# P_JTAG_EEPROM.net
KiCad netlist of a schematic drawn in Altium Designer
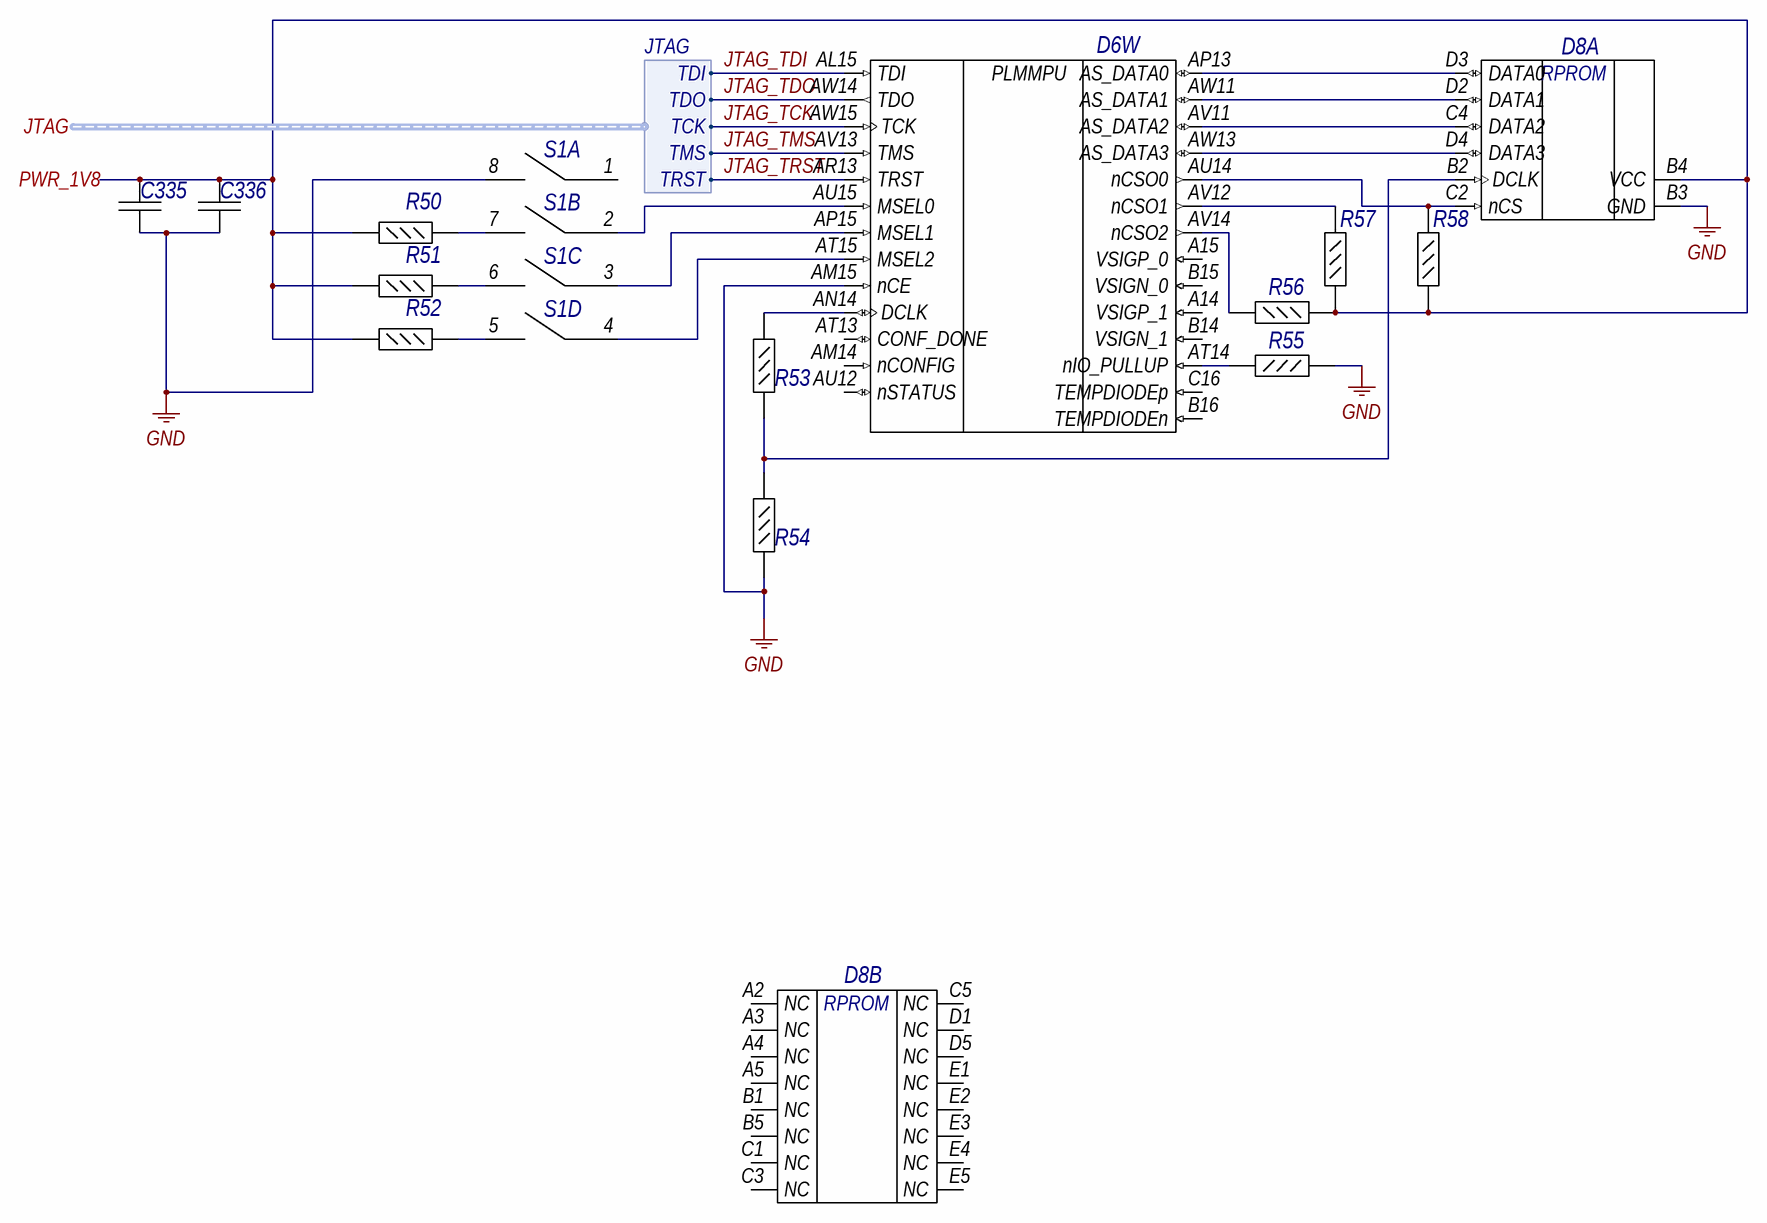
[diagram p0: P_JTAG_EEPROM.SchDoc]

(export (version "E")
  (design (tool "Eeschema 10.0.6"))
  (components
    (comp (ref "C335")
      (value "C1005X7R1E104M")
      (footprint "CAPC1005X55X10LL05")
      (description "Chip Capacitor, 0.1 uF, +/- 20%, 25 V, -55 to 125 degC, 0402 (1005 Metric), RoHS, Tape and Reel")
      (fields (field (name "TOLERANCE") "20%"))
      (libsource (lib "MiniPC DB") (part "CAP_NP"))
    )
    (comp (ref "C336")
      (value "C1005X7R1E104M")
      (footprint "CAPC1005X55X10LL05")
      (description "Chip Capacitor, 0.1 uF, +/- 20%, 25 V, -55 to 125 degC, 0402 (1005 Metric), RoHS, Tape and Reel")
      (fields (field (name "TOLERANCE") "20%"))
      (libsource (lib "MiniPC DB") (part "CAP_NP"))
    )
    (comp (ref "D6")
      (value "10AS066N3F40E2SGE2")
      (footprint "ALTR-FBGA1517_A-350")
      (libsource (lib "MiniPC DB") (part "10AS066N3F40"))
    )
    (comp (ref "D8")
      (value "EPCQL1024F24IN")
      (footprint "ALTR-FBGA24_A-130")
      (description "EPCQ-L Serial Configuration Device, 1.8 V, -40 to 85 degC, 24-Pin FBGA, RoHS, Tray")
      (fields (field (name "MANUFACTURER") "Altera"))
      (libsource (lib "MiniPC DB") (part "EPCQLXXX"))
    )
    (comp (ref "R50")
      (value "ERJ-2RKF1001X")
      (footprint "RESC1005X40X25LL05T05")
      (description "Chip Resistor, 1 KOhm, +/- 1%, 100 mW, -55 to 155 degC, 0402 (1005 Metric), RoHS, Tape and Reel")
      (fields (field (name "TOLERANCE") "1%") (field (name "MANUFACTURER") "Basic Passives"))
      (libsource (lib "MiniPC DB") (part "RES-0.05"))
    )
    (comp (ref "R51")
      (value "ERJ-2RKF1001X")
      (footprint "RESC1005X40X25LL05T05")
      (description "Chip Resistor, 1 KOhm, +/- 1%, 100 mW, -55 to 155 degC, 0402 (1005 Metric), RoHS, Tape and Reel")
      (fields (field (name "TOLERANCE") "1%") (field (name "MANUFACTURER") "Basic Passives"))
      (libsource (lib "MiniPC DB") (part "RES-0.05"))
    )
    (comp (ref "R52")
      (value "ERJ-2RKF1001X")
      (footprint "RESC1005X40X25LL05T05")
      (description "Chip Resistor, 1 KOhm, +/- 1%, 100 mW, -55 to 155 degC, 0402 (1005 Metric), RoHS, Tape and Reel")
      (fields (field (name "TOLERANCE") "1%") (field (name "MANUFACTURER") "Basic Passives"))
      (libsource (lib "MiniPC DB") (part "RES-0.05"))
    )
    (comp (ref "R53")
      (value "ERJ-2RKF1002X")
      (footprint "RESC1005X40X25LL05T05")
      (description "Chip Resistor, 10 KOhm, +/- 1%, 100 mW, -55 to 155 degC, 0402 (1005 Metric), RoHS, Tape and Reel")
      (fields (field (name "TOLERANCE") "1%") (field (name "MANUFACTURER") "Basic Passives"))
      (libsource (lib "") (part "RES-0.05_1"))
    )
    (comp (ref "R54")
      (value "ERJ-2RKF1002X")
      (footprint "RESC1005X40X25LL05T05")
      (description "Chip Resistor, 10 KOhm, +/- 1%, 100 mW, -55 to 155 degC, 0402 (1005 Metric), RoHS, Tape and Reel")
      (fields (field (name "TOLERANCE") "1%") (field (name "MANUFACTURER") "Basic Passives"))
      (libsource (lib "") (part "RES-0.05_1"))
    )
    (comp (ref "R55")
      (value "ERJ-2GE0R00X")
      (footprint "RESC1005X40X25LL05T05")
      (description "Chip Resistor, 0 mOhm, +/- 5%, 100 mW, -55 to 155 degC, 0402 (1005 Metric), RoHS, Tape and Reel")
      (fields (field (name "TOLERANCE") "5%") (field (name "MANUFACTURER") "Basic Passives"))
      (libsource (lib "") (part "RES-0.05_3"))
    )
    (comp (ref "R56")
      (value "ERJ-2RKF1002X")
      (footprint "RESC1005X40X25LL05T05")
      (description "Chip Resistor, 10 KOhm, +/- 1%, 100 mW, -55 to 155 degC, 0402 (1005 Metric), RoHS, Tape and Reel")
      (fields (field (name "TOLERANCE") "1%") (field (name "MANUFACTURER") "Basic Passives"))
      (libsource (lib "") (part "RES-0.05_2"))
    )
    (comp (ref "R57")
      (value "ERJ-2RKF1002X")
      (footprint "RESC1005X40X25LL05T05")
      (description "Chip Resistor, 10 KOhm, +/- 1%, 100 mW, -55 to 155 degC, 0402 (1005 Metric), RoHS, Tape and Reel")
      (fields (field (name "TOLERANCE") "1%") (field (name "MANUFACTURER") "Basic Passives"))
      (libsource (lib "") (part "RES-0.05_1"))
    )
    (comp (ref "R58")
      (value "ERJ-2RKF1002X")
      (footprint "RESC1005X40X25LL05T05")
      (description "Chip Resistor, 10 KOhm, +/- 1%, 100 mW, -55 to 155 degC, 0402 (1005 Metric), RoHS, Tape and Reel")
      (fields (field (name "TOLERANCE") "1%") (field (name "MANUFACTURER") "Basic Passives"))
      (libsource (lib "") (part "RES-0.05_1"))
    )
    (comp (ref "S1")
      (value "416131160804")
      (footprint "416131160804")
      (description "WS-DISV 1.27 mm small compact SMD Dip Switch with top tape")
      (fields (field (name "MANUFACTURER") "Wuerth Elektronik"))
      (libsource (lib "MiniPC DB") (part "SW_SPST_4"))
    )
  )
  (nets
    (net (code "2") (name "/JTAG_TCK") (class "Default")
      (node (ref "D6") (pin "AW15") (pinfunction "TCK_AW15") (pintype "input"))
    )
    (net (code "3") (name "/JTAG_TDI") (class "Default")
      (node (ref "D6") (pin "AL15") (pinfunction "TDI_AL15") (pintype "input"))
    )
    (net (code "4") (name "/JTAG_TDO") (class "Default")
      (node (ref "D6") (pin "AW14") (pinfunction "TDO_AW14") (pintype "output"))
    )
    (net (code "5") (name "/JTAG_TMS") (class "Default")
      (node (ref "D6") (pin "AV13") (pinfunction "TMS_AV13") (pintype "input"))
    )
    (net (code "6") (name "/JTAG_TRST") (class "Default")
      (node (ref "D6") (pin "AR13") (pinfunction "TRST_AR13") (pintype "input"))
    )
    (net (code "7") (name "/PWR_1V8") (class "Default")
      (node (ref "C335") (pin "2") (pinfunction "2_2") (pintype "passive"))
      (node (ref "C336") (pin "2") (pinfunction "2_2") (pintype "passive"))
      (node (ref "D8") (pin "B4") (pinfunction "VCC_B4") (pintype "passive"))
      (node (ref "R50") (pin "1") (pinfunction "1_1") (pintype "passive"))
      (node (ref "R51") (pin "1") (pinfunction "1_1") (pintype "passive"))
      (node (ref "R52") (pin "1") (pinfunction "1_1") (pintype "passive"))
      (node (ref "R56") (pin "1") (pinfunction "1_1") (pintype "passive"))
      (node (ref "R57") (pin "1") (pinfunction "1_1") (pintype "passive"))
      (node (ref "R58") (pin "1") (pinfunction "1_1") (pintype "passive"))
    )
    (net (code "9") (name "GND") (class "Default")
      (node (ref "C335") (pin "1") (pinfunction "1_1") (pintype "passive"))
      (node (ref "C336") (pin "1") (pinfunction "1_1") (pintype "passive"))
      (node (ref "D6") (pin "AM15") (pinfunction "nCE_AM15") (pintype "input"))
      (node (ref "D8") (pin "B3") (pinfunction "GND_B3") (pintype "passive"))
      (node (ref "R54") (pin "1") (pinfunction "1_1") (pintype "passive"))
      (node (ref "R55") (pin "1") (pinfunction "1_1") (pintype "passive"))
      (node (ref "S1") (pin "8") (pinfunction "8_8") (pintype "passive"))
    )
    (net (code "10") (name "Net-(D6W-AS_DATA0)") (class "Default")
      (node (ref "D6") (pin "AP13") (pinfunction "AS_DATA0_AP13") (pintype "bidirectional"))
      (node (ref "D8") (pin "D3") (pinfunction "DATA0_D3") (pintype "bidirectional"))
    )
    (net (code "11") (name "Net-(D6W-AS_DATA1)") (class "Default")
      (node (ref "D6") (pin "AW11") (pinfunction "AS_DATA1_AW11") (pintype "bidirectional"))
      (node (ref "D8") (pin "D2") (pinfunction "DATA1_D2") (pintype "bidirectional"))
    )
    (net (code "12") (name "Net-(D6W-AS_DATA2)") (class "Default")
      (node (ref "D6") (pin "AV11") (pinfunction "AS_DATA2_AV11") (pintype "bidirectional"))
      (node (ref "D8") (pin "C4") (pinfunction "DATA2_C4") (pintype "bidirectional"))
    )
    (net (code "13") (name "Net-(D6W-AS_DATA3)") (class "Default")
      (node (ref "D6") (pin "AW13") (pinfunction "AS_DATA3_AW13") (pintype "bidirectional"))
      (node (ref "D8") (pin "D4") (pinfunction "DATA3_D4") (pintype "bidirectional"))
    )
    (net (code "14") (name "Net-(D6W-DCLK)") (class "Default")
      (node (ref "D6") (pin "AN14") (pinfunction "DCLK_AN14") (pintype "bidirectional"))
      (node (ref "R53") (pin "2") (pinfunction "2_2") (pintype "passive"))
    )
    (net (code "15") (name "Net-(D6W-MSEL0)") (class "Default")
      (node (ref "D6") (pin "AU15") (pinfunction "MSEL0_AU15") (pintype "input"))
      (node (ref "S1") (pin "2") (pinfunction "2_2") (pintype "passive"))
    )
    (net (code "16") (name "Net-(D6W-MSEL1)") (class "Default")
      (node (ref "D6") (pin "AP15") (pinfunction "MSEL1_AP15") (pintype "input"))
      (node (ref "S1") (pin "3") (pinfunction "3_3") (pintype "passive"))
    )
    (net (code "17") (name "Net-(D6W-MSEL2)") (class "Default")
      (node (ref "D6") (pin "AT15") (pinfunction "MSEL2_AT15") (pintype "input"))
      (node (ref "S1") (pin "4") (pinfunction "4_4") (pintype "passive"))
    )
    (net (code "18") (name "Net-(D6W-nCSO0)") (class "Default")
      (node (ref "D6") (pin "AU14") (pinfunction "nCSO0_AU14") (pintype "output"))
      (node (ref "D8") (pin "C2") (pinfunction "nCS_C2") (pintype "input"))
      (node (ref "R58") (pin "2") (pinfunction "2_2") (pintype "passive"))
    )
    (net (code "19") (name "Net-(D6W-nCSO1)") (class "Default")
      (node (ref "D6") (pin "AV12") (pinfunction "nCSO1_AV12") (pintype "output"))
      (node (ref "R57") (pin "2") (pinfunction "2_2") (pintype "passive"))
    )
    (net (code "20") (name "Net-(D6W-nCSO2)") (class "Default")
      (node (ref "D6") (pin "AV14") (pinfunction "nCSO2_AV14") (pintype "output"))
      (node (ref "R56") (pin "2") (pinfunction "2_2") (pintype "passive"))
    )
    (net (code "21") (name "Net-(D6W-nIO_PULLUP)") (class "Default")
      (node (ref "D6") (pin "AT14") (pinfunction "nIO_PULLUP_AT14") (pintype "input"))
      (node (ref "R55") (pin "2") (pinfunction "2_2") (pintype "passive"))
    )
    (net (code "22") (name "Net-(D8A-DCLK)") (class "Default")
      (node (ref "D8") (pin "B2") (pinfunction "DCLK_B2") (pintype "input"))
      (node (ref "R53") (pin "1") (pinfunction "1_1") (pintype "passive"))
      (node (ref "R54") (pin "2") (pinfunction "2_2") (pintype "passive"))
    )
    (net (code "23") (name "Net-(R50-Pad2)") (class "Default")
      (node (ref "R50") (pin "2") (pinfunction "2_2") (pintype "passive"))
      (node (ref "S1") (pin "7") (pinfunction "7_7") (pintype "passive"))
    )
    (net (code "24") (name "Net-(R51-Pad2)") (class "Default")
      (node (ref "R51") (pin "2") (pinfunction "2_2") (pintype "passive"))
      (node (ref "S1") (pin "6") (pinfunction "6_6") (pintype "passive"))
    )
    (net (code "25") (name "Net-(R52-Pad2)") (class "Default")
      (node (ref "R52") (pin "2") (pinfunction "2_2") (pintype "passive"))
      (node (ref "S1") (pin "5") (pinfunction "5_5") (pintype "passive"))
    )
    (net (code "26") (name "unconnected-(D6W-CONF_DONE-PadAT13)") (class "Default")
      (node (ref "D6") (pin "AT13") (pinfunction "CONF_DONE_AT13") (pintype "bidirectional"))
    )
    (net (code "27") (name "unconnected-(D6W-TEMPDIODEn-PadB16)") (class "Default")
      (node (ref "D6") (pin "B16") (pinfunction "TEMPDIODEn_B16") (pintype "input"))
    )
    (net (code "28") (name "unconnected-(D6W-TEMPDIODEp-PadC16)") (class "Default")
      (node (ref "D6") (pin "C16") (pinfunction "TEMPDIODEp_C16") (pintype "input"))
    )
    (net (code "29") (name "unconnected-(D6W-VSIGN_0-PadB15)") (class "Default")
      (node (ref "D6") (pin "B15") (pinfunction "VSIGN_0_B15") (pintype "input"))
    )
    (net (code "30") (name "unconnected-(D6W-VSIGN_1-PadB14)") (class "Default")
      (node (ref "D6") (pin "B14") (pinfunction "VSIGN_1_B14") (pintype "input"))
    )
    (net (code "31") (name "unconnected-(D6W-VSIGP_0-PadA15)") (class "Default")
      (node (ref "D6") (pin "A15") (pinfunction "VSIGP_0_A15") (pintype "input"))
    )
    (net (code "32") (name "unconnected-(D6W-VSIGP_1-PadA14)") (class "Default")
      (node (ref "D6") (pin "A14") (pinfunction "VSIGP_1_A14") (pintype "input"))
    )
    (net (code "33") (name "unconnected-(D6W-nCONFIG-PadAM14)") (class "Default")
      (node (ref "D6") (pin "AM14") (pinfunction "nCONFIG_AM14") (pintype "input"))
    )
    (net (code "34") (name "unconnected-(D6W-nSTATUS-PadAU12)") (class "Default")
      (node (ref "D6") (pin "AU12") (pinfunction "nSTATUS_AU12") (pintype "bidirectional"))
    )
    (net (code "35") (name "unconnected-(D8B-NC-PadA2)") (class "Default")
      (node (ref "D8") (pin "A2") (pinfunction "NC_A2") (pintype "passive"))
    )
    (net (code "36") (name "unconnected-(D8B-NC-PadA3)") (class "Default")
      (node (ref "D8") (pin "A3") (pinfunction "NC_A3") (pintype "passive"))
    )
    (net (code "37") (name "unconnected-(D8B-NC-PadA4)") (class "Default")
      (node (ref "D8") (pin "A4") (pinfunction "NC_A4") (pintype "passive"))
    )
    (net (code "38") (name "unconnected-(D8B-NC-PadA5)") (class "Default")
      (node (ref "D8") (pin "A5") (pinfunction "NC_A5") (pintype "passive"))
    )
    (net (code "39") (name "unconnected-(D8B-NC-PadB1)") (class "Default")
      (node (ref "D8") (pin "B1") (pinfunction "NC_B1") (pintype "passive"))
    )
    (net (code "40") (name "unconnected-(D8B-NC-PadB5)") (class "Default")
      (node (ref "D8") (pin "B5") (pinfunction "NC_B5") (pintype "passive"))
    )
    (net (code "41") (name "unconnected-(D8B-NC-PadC1)") (class "Default")
      (node (ref "D8") (pin "C1") (pinfunction "NC_C1") (pintype "passive"))
    )
    (net (code "42") (name "unconnected-(D8B-NC-PadC3)") (class "Default")
      (node (ref "D8") (pin "C3") (pinfunction "NC_C3") (pintype "passive"))
    )
    (net (code "43") (name "unconnected-(D8B-NC-PadC5)") (class "Default")
      (node (ref "D8") (pin "C5") (pinfunction "NC_C5") (pintype "passive"))
    )
    (net (code "44") (name "unconnected-(D8B-NC-PadD1)") (class "Default")
      (node (ref "D8") (pin "D1") (pinfunction "NC_D1") (pintype "passive"))
    )
    (net (code "45") (name "unconnected-(D8B-NC-PadD5)") (class "Default")
      (node (ref "D8") (pin "D5") (pinfunction "NC_D5") (pintype "passive"))
    )
    (net (code "46") (name "unconnected-(D8B-NC-PadE1)") (class "Default")
      (node (ref "D8") (pin "E1") (pinfunction "NC_E1") (pintype "passive"))
    )
    (net (code "47") (name "unconnected-(D8B-NC-PadE2)") (class "Default")
      (node (ref "D8") (pin "E2") (pinfunction "NC_E2") (pintype "passive"))
    )
    (net (code "48") (name "unconnected-(D8B-NC-PadE3)") (class "Default")
      (node (ref "D8") (pin "E3") (pinfunction "NC_E3") (pintype "passive"))
    )
    (net (code "49") (name "unconnected-(D8B-NC-PadE4)") (class "Default")
      (node (ref "D8") (pin "E4") (pinfunction "NC_E4") (pintype "passive"))
    )
    (net (code "50") (name "unconnected-(D8B-NC-PadE5)") (class "Default")
      (node (ref "D8") (pin "E5") (pinfunction "NC_E5") (pintype "passive"))
    )
    (net (code "51") (name "unconnected-(S1-Pad1)") (class "Default")
      (node (ref "S1") (pin "1") (pinfunction "1_1") (pintype "passive"))
    )
  )
)
